# PCB-REMCON.net
KiCad netlist of a schematic drawn in EAGLE
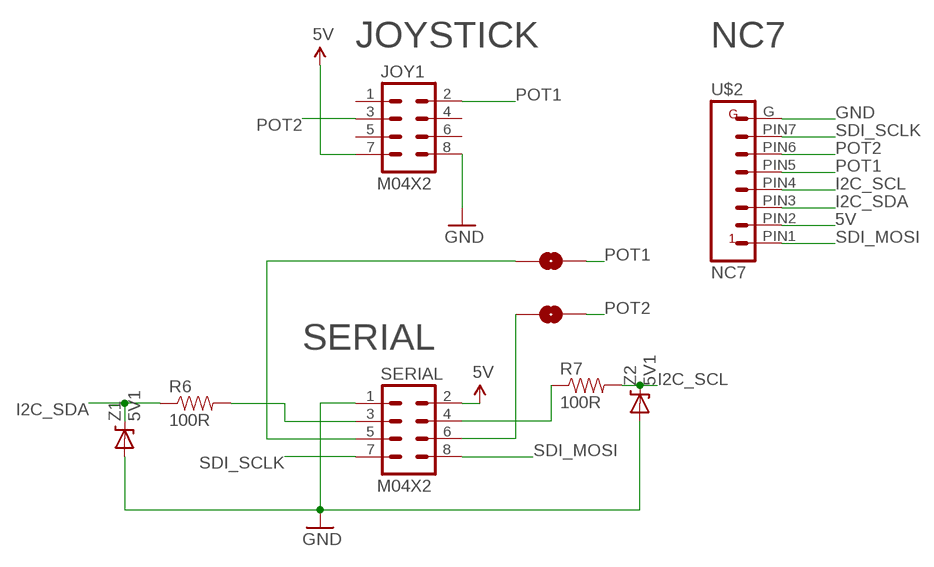
[diagram p0: schematic, sheet 1]

(export (version "E")
  (design (tool "Eeschema 10.0.6"))
  (components
    (comp (ref "JOY1")
      (value "M04X2")
      (footprint "eagle-import:2X4")
      (libsource (lib "eagle-import") (part "M04X2"))
    )
    (comp (ref "R6")
      (value "100R")
      (footprint "eagle-import:0603-RES")
      (libsource (lib "eagle-import") (part "RESISTOR0603-RES"))
    )
    (comp (ref "R7")
      (value "100R")
      (footprint "eagle-import:0603-RES")
      (libsource (lib "eagle-import") (part "RESISTOR0603-RES"))
    )
    (comp (ref "SCLK->D1")
      (value "SOLDERJUMPERNC")
      (footprint "eagle-import:SJ_2S")
      (libsource (lib "eagle-import") (part "SOLDERJUMPERNC"))
    )
    (comp (ref "SCLK->D5")
      (value "SOLDERJUMPERNC")
      (footprint "eagle-import:SJ_2S")
      (libsource (lib "eagle-import") (part "SOLDERJUMPERNC"))
    )
    (comp (ref "SERIAL")
      (value "M04X2")
      (footprint "eagle-import:2X4")
      (libsource (lib "eagle-import") (part "M04X2"))
    )
    (comp (ref "U$2")
      (value "NC7")
      (footprint "eagle-import:NC7-MD-L1")
      (libsource (lib "eagle-import") (part "NC7"))
    )
    (comp (ref "Z1")
      (value "5V1")
      (footprint "eagle-import:DIODE-ZENER")
      (libsource (lib "eagle-import") (part "DIODE-ZENERPTH"))
    )
    (comp (ref "Z2")
      (value "5V1")
      (footprint "eagle-import:DIODE-ZENER")
      (libsource (lib "eagle-import") (part "DIODE-ZENERPTH"))
    )
  )
  (nets
    (net (code "1") (name "/I2C_SCL") (class "Default")
      (node (ref "R7") (pin "2") (pinfunction "2_2") (pintype "passive"))
      (node (ref "U$2") (pin "PIN4") (pinfunction "4_PIN4") (pintype "passive"))
      (node (ref "Z2") (pin "P$1") (pinfunction "C_P$1") (pintype "passive"))
    )
    (net (code "2") (name "/I2C_SDA") (class "Default")
      (node (ref "R6") (pin "1") (pinfunction "1_1") (pintype "passive"))
      (node (ref "U$2") (pin "PIN3") (pinfunction "3_PIN3") (pintype "passive"))
      (node (ref "Z1") (pin "P$1") (pinfunction "C_P$1") (pintype "passive"))
    )
    (net (code "3") (name "/POT1") (class "Default")
      (node (ref "JOY1") (pin "2") (pinfunction "2_2") (pintype "passive"))
      (node (ref "SCLK->D1") (pin "2") (pinfunction "2_2") (pintype "passive"))
      (node (ref "U$2") (pin "PIN5") (pinfunction "5_PIN5") (pintype "passive"))
    )
    (net (code "4") (name "/POT2") (class "Default")
      (node (ref "JOY1") (pin "3") (pinfunction "3_3") (pintype "passive"))
      (node (ref "SCLK->D5") (pin "2") (pinfunction "2_2") (pintype "passive"))
      (node (ref "U$2") (pin "PIN6") (pinfunction "6_PIN6") (pintype "passive"))
    )
    (net (code "5") (name "/SDI_MOSI") (class "Default")
      (node (ref "SERIAL") (pin "8") (pinfunction "8_8") (pintype "passive"))
      (node (ref "U$2") (pin "PIN1") (pinfunction "1_PIN1") (pintype "passive"))
    )
    (net (code "6") (name "/SDI_SCLK") (class "Default")
      (node (ref "SERIAL") (pin "7") (pinfunction "7_7") (pintype "passive"))
      (node (ref "U$2") (pin "PIN7") (pinfunction "7_PIN7") (pintype "passive"))
    )
    (net (code "7") (name "5V") (class "Default")
      (node (ref "JOY1") (pin "7") (pinfunction "7_7") (pintype "passive"))
      (node (ref "SERIAL") (pin "2") (pinfunction "2_2") (pintype "passive"))
      (node (ref "U$2") (pin "PIN2") (pinfunction "2_PIN2") (pintype "passive"))
    )
    (net (code "8") (name "GND") (class "Default")
      (node (ref "JOY1") (pin "8") (pinfunction "8_8") (pintype "passive"))
      (node (ref "SERIAL") (pin "1") (pinfunction "1_1") (pintype "passive"))
      (node (ref "U$2") (pin "G") (pinfunction "G_G") (pintype "passive"))
      (node (ref "Z1") (pin "P$2") (pinfunction "A_P$2") (pintype "passive"))
      (node (ref "Z2") (pin "P$2") (pinfunction "A_P$2") (pintype "passive"))
    )
    (net (code "9") (name "Net-(R6-Pad2)") (class "Default")
      (node (ref "R6") (pin "2") (pinfunction "2_2") (pintype "passive"))
      (node (ref "SERIAL") (pin "3") (pinfunction "3_3") (pintype "passive"))
    )
    (net (code "10") (name "Net-(R7-Pad1)") (class "Default")
      (node (ref "R7") (pin "1") (pinfunction "1_1") (pintype "passive"))
      (node (ref "SERIAL") (pin "4") (pinfunction "4_4") (pintype "passive"))
    )
    (net (code "11") (name "Net-(SCLK->D1-Pad1)") (class "Default")
      (node (ref "SCLK->D1") (pin "1") (pinfunction "1_1") (pintype "passive"))
      (node (ref "SERIAL") (pin "5") (pinfunction "5_5") (pintype "passive"))
    )
    (net (code "12") (name "Net-(SCLK->D5-Pad1)") (class "Default")
      (node (ref "SCLK->D5") (pin "1") (pinfunction "1_1") (pintype "passive"))
      (node (ref "SERIAL") (pin "6") (pinfunction "6_6") (pintype "passive"))
    )
    (net (code "13") (name "unconnected-(JOY1-Pad1)") (class "Default")
      (node (ref "JOY1") (pin "1") (pinfunction "1_1") (pintype "passive"))
    )
    (net (code "14") (name "unconnected-(JOY1-Pad4)") (class "Default")
      (node (ref "JOY1") (pin "4") (pinfunction "4_4") (pintype "passive"))
    )
    (net (code "15") (name "unconnected-(JOY1-Pad5)") (class "Default")
      (node (ref "JOY1") (pin "5") (pinfunction "5_5") (pintype "passive"))
    )
    (net (code "16") (name "unconnected-(JOY1-Pad6)") (class "Default")
      (node (ref "JOY1") (pin "6") (pinfunction "6_6") (pintype "passive"))
    )
  )
)
